# SNES_AddOn1Chip.net
KiCad netlist of a schematic drawn in EAGLE
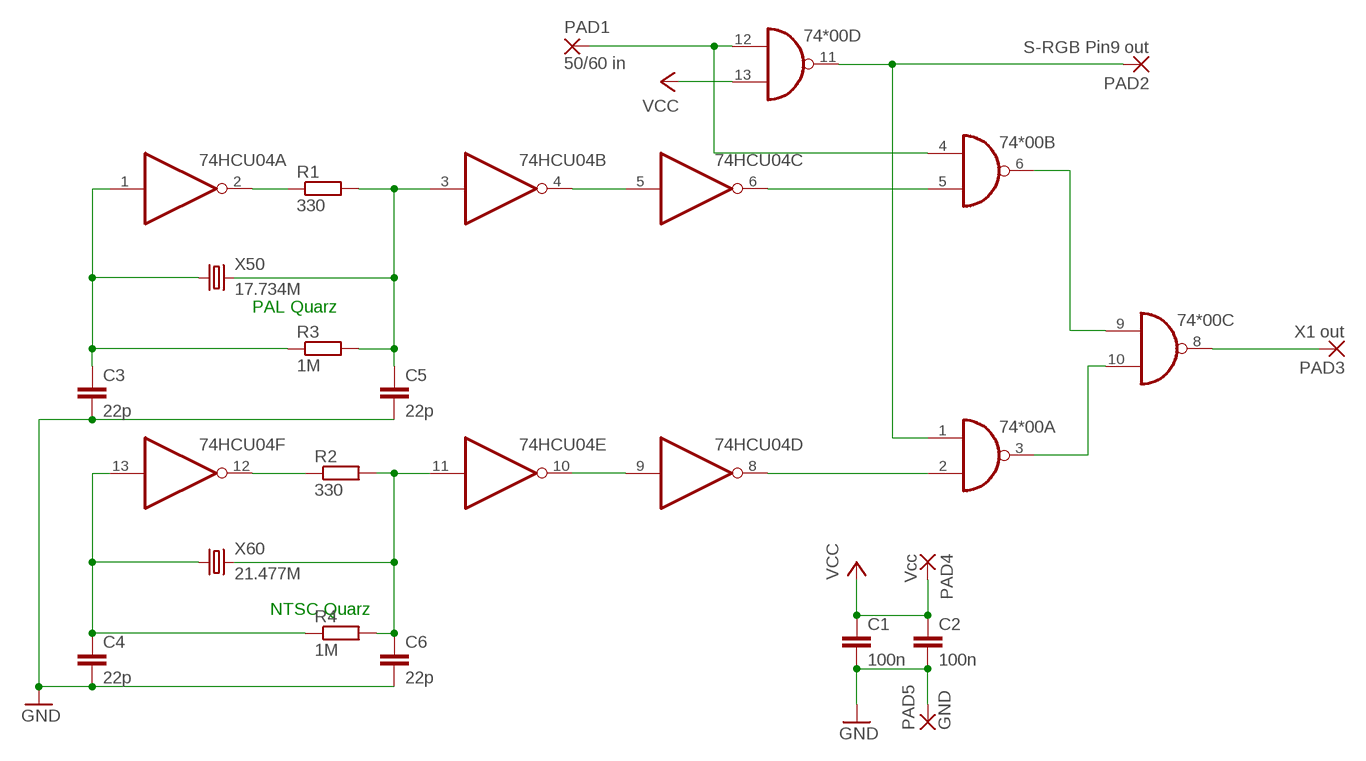
[diagram p0: schematic, sheet 1]

(export (version "E")
  (design (tool "Eeschema 10.0.6"))
  (components
    (comp (ref "74*00")
      (value "7400D")
      (footprint "eagle-import:SO14")
      (libsource (lib "eagle-import") (part "7400D"))
    )
    (comp (ref "74HCU04")
      (value "74HC04D")
      (footprint "eagle-import:SO14")
      (libsource (lib "eagle-import") (part "7404DHC"))
    )
    (comp (ref "C1")
      (value "100n")
      (footprint "eagle-import:Z0805")
      (libsource (lib "eagle-import") (part "C0805"))
    )
    (comp (ref "C2")
      (value "100n")
      (footprint "eagle-import:Z0805")
      (libsource (lib "eagle-import") (part "C0805"))
    )
    (comp (ref "C3")
      (value "22p")
      (footprint "eagle-import:Z0805")
      (libsource (lib "eagle-import") (part "C0805"))
    )
    (comp (ref "C4")
      (value "22p")
      (footprint "eagle-import:Z0805")
      (libsource (lib "eagle-import") (part "C0805"))
    )
    (comp (ref "C5")
      (value "22p")
      (footprint "eagle-import:Z0805")
      (libsource (lib "eagle-import") (part "C0805"))
    )
    (comp (ref "C6")
      (value "22p")
      (footprint "eagle-import:Z0805")
      (libsource (lib "eagle-import") (part "C0805"))
    )
    (comp (ref "PAD1")
      (value "50/60 in")
      (footprint "eagle-import:SMD1,27-2,54")
      (libsource (lib "eagle-import") (part "SMD2"))
    )
    (comp (ref "PAD2")
      (value "S-RGB Pin9 out")
      (footprint "eagle-import:SMD1,27-2,54")
      (libsource (lib "eagle-import") (part "SMD2"))
    )
    (comp (ref "PAD3")
      (value "X1 out")
      (footprint "eagle-import:SMD1,27-2,54")
      (libsource (lib "eagle-import") (part "SMD2"))
    )
    (comp (ref "PAD4")
      (value "Vcc")
      (footprint "eagle-import:SMD2,54-5,08")
      (libsource (lib "eagle-import") (part "SMD5"))
    )
    (comp (ref "PAD5")
      (value "GND")
      (footprint "eagle-import:SMD2,54-5,08")
      (libsource (lib "eagle-import") (part "SMD5"))
    )
    (comp (ref "R1")
      (value "330")
      (footprint "eagle-import:Z0805")
      (libsource (lib "eagle-import") (part "R0805"))
    )
    (comp (ref "R2")
      (value "330")
      (footprint "eagle-import:Z0805")
      (libsource (lib "eagle-import") (part "R0805"))
    )
    (comp (ref "R3")
      (value "1M")
      (footprint "eagle-import:Z0805")
      (libsource (lib "eagle-import") (part "R0805"))
    )
    (comp (ref "R4")
      (value "1M")
      (footprint "eagle-import:Z0805")
      (libsource (lib "eagle-import") (part "R0805"))
    )
    (comp (ref "X50")
      (value "17.734M")
      (footprint "eagle-import:MY_SMD_CRYSTAL2")
      (libsource (lib "eagle-import") (part "MY_CRYSTALS"))
    )
    (comp (ref "X60")
      (value "21.477M")
      (footprint "eagle-import:MY_SMD_CRYSTAL2")
      (libsource (lib "eagle-import") (part "MY_CRYSTALS"))
    )
  )
  (nets
    (net (code "1") (name "GND") (class "Default")
      (node (ref "C1") (pin "2") (pinfunction "2_2") (pintype "passive"))
      (node (ref "C2") (pin "2") (pinfunction "2_2") (pintype "passive"))
      (node (ref "C3") (pin "2") (pinfunction "2_2") (pintype "passive"))
      (node (ref "C4") (pin "2") (pinfunction "2_2") (pintype "passive"))
      (node (ref "C5") (pin "2") (pinfunction "2_2") (pintype "passive"))
      (node (ref "C6") (pin "2") (pinfunction "2_2") (pintype "passive"))
      (node (ref "PAD5") (pin "1") (pinfunction "P_1") (pintype "passive"))
    )
    (net (code "2") (name "Net-(74*00A-I0)") (class "Default")
      (node (ref "74*00") (pin "1") (pinfunction "I0_1") (pintype "input"))
      (node (ref "74*00") (pin "11") (pinfunction "O_11") (pintype "output"))
      (node (ref "PAD2") (pin "1") (pinfunction "P_1") (pintype "passive"))
    )
    (net (code "3") (name "Net-(74*00A-I1)") (class "Default")
      (node (ref "74*00") (pin "2") (pinfunction "I1_2") (pintype "input"))
      (node (ref "74HCU04") (pin "8") (pinfunction "O_8") (pintype "output"))
    )
    (net (code "4") (name "Net-(74*00A-O)") (class "Default")
      (node (ref "74*00") (pin "10") (pinfunction "I1_10") (pintype "input"))
      (node (ref "74*00") (pin "3") (pinfunction "O_3") (pintype "output"))
    )
    (net (code "5") (name "Net-(74*00B-I0)") (class "Default")
      (node (ref "74*00") (pin "12") (pinfunction "I0_12") (pintype "input"))
      (node (ref "74*00") (pin "4") (pinfunction "I0_4") (pintype "input"))
      (node (ref "PAD1") (pin "1") (pinfunction "P_1") (pintype "passive"))
    )
    (net (code "6") (name "Net-(74*00B-I1)") (class "Default")
      (node (ref "74*00") (pin "5") (pinfunction "I1_5") (pintype "input"))
      (node (ref "74HCU04") (pin "6") (pinfunction "O_6") (pintype "output"))
    )
    (net (code "7") (name "Net-(74*00B-O)") (class "Default")
      (node (ref "74*00") (pin "6") (pinfunction "O_6") (pintype "output"))
      (node (ref "74*00") (pin "9") (pinfunction "I0_9") (pintype "input"))
    )
    (net (code "8") (name "Net-(74*00C-O)") (class "Default")
      (node (ref "74*00") (pin "8") (pinfunction "O_8") (pintype "output"))
      (node (ref "PAD3") (pin "1") (pinfunction "P_1") (pintype "passive"))
    )
    (net (code "9") (name "Net-(74HCU04A-I)") (class "Default")
      (node (ref "74HCU04") (pin "1") (pinfunction "I_1") (pintype "input"))
      (node (ref "C3") (pin "1") (pinfunction "1_1") (pintype "passive"))
      (node (ref "R3") (pin "1") (pinfunction "1_1") (pintype "passive"))
      (node (ref "X50") (pin "1") (pinfunction "1_1") (pintype "passive"))
    )
    (net (code "10") (name "Net-(74HCU04A-O)") (class "Default")
      (node (ref "74HCU04") (pin "2") (pinfunction "O_2") (pintype "output"))
      (node (ref "R1") (pin "1") (pinfunction "1_1") (pintype "passive"))
    )
    (net (code "11") (name "Net-(74HCU04B-I)") (class "Default")
      (node (ref "74HCU04") (pin "3") (pinfunction "I_3") (pintype "input"))
      (node (ref "C5") (pin "1") (pinfunction "1_1") (pintype "passive"))
      (node (ref "R1") (pin "2") (pinfunction "2_2") (pintype "passive"))
      (node (ref "R3") (pin "2") (pinfunction "2_2") (pintype "passive"))
      (node (ref "X50") (pin "2") (pinfunction "2_2") (pintype "passive"))
    )
    (net (code "12") (name "Net-(74HCU04B-O)") (class "Default")
      (node (ref "74HCU04") (pin "4") (pinfunction "O_4") (pintype "output"))
      (node (ref "74HCU04") (pin "5") (pinfunction "I_5") (pintype "input"))
    )
    (net (code "13") (name "Net-(74HCU04D-I)") (class "Default")
      (node (ref "74HCU04") (pin "10") (pinfunction "O_10") (pintype "output"))
      (node (ref "74HCU04") (pin "9") (pinfunction "I_9") (pintype "input"))
    )
    (net (code "14") (name "Net-(74HCU04E-I)") (class "Default")
      (node (ref "74HCU04") (pin "11") (pinfunction "I_11") (pintype "input"))
      (node (ref "C6") (pin "1") (pinfunction "1_1") (pintype "passive"))
      (node (ref "R2") (pin "2") (pinfunction "2_2") (pintype "passive"))
      (node (ref "R4") (pin "2") (pinfunction "2_2") (pintype "passive"))
      (node (ref "X60") (pin "2") (pinfunction "2_2") (pintype "passive"))
    )
    (net (code "15") (name "Net-(74HCU04F-I)") (class "Default")
      (node (ref "74HCU04") (pin "13") (pinfunction "I_13") (pintype "input"))
      (node (ref "C4") (pin "1") (pinfunction "1_1") (pintype "passive"))
      (node (ref "R4") (pin "1") (pinfunction "1_1") (pintype "passive"))
      (node (ref "X60") (pin "1") (pinfunction "1_1") (pintype "passive"))
    )
    (net (code "16") (name "Net-(74HCU04F-O)") (class "Default")
      (node (ref "74HCU04") (pin "12") (pinfunction "O_12") (pintype "output"))
      (node (ref "R2") (pin "1") (pinfunction "1_1") (pintype "passive"))
    )
    (net (code "17") (name "VCC") (class "Default")
      (node (ref "74*00") (pin "13") (pinfunction "I1_13") (pintype "input"))
      (node (ref "C1") (pin "1") (pinfunction "1_1") (pintype "passive"))
      (node (ref "C2") (pin "1") (pinfunction "1_1") (pintype "passive"))
      (node (ref "PAD4") (pin "1") (pinfunction "P_1") (pintype "passive"))
    )
  )
)
